# VisualEar-2_0.net
KiCad netlist of a schematic drawn in EAGLE
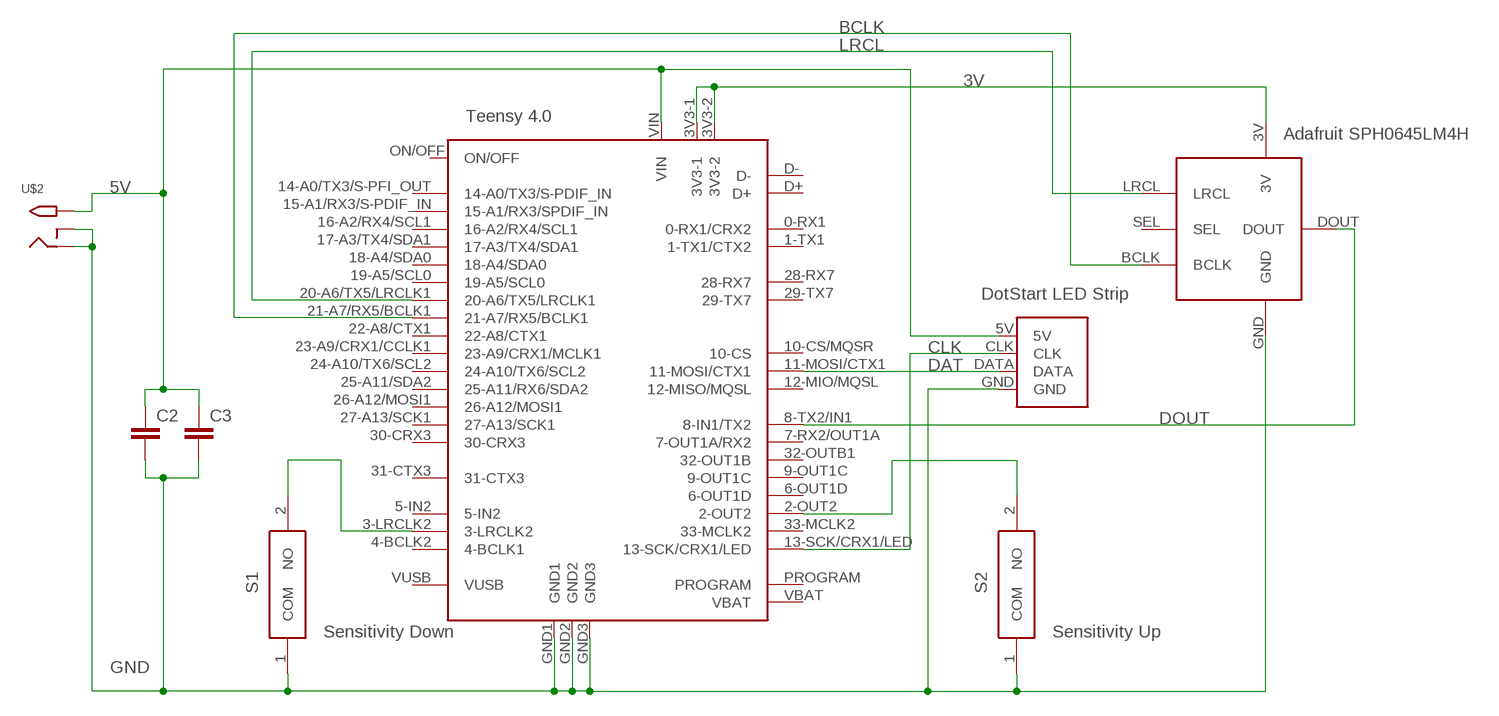
[diagram p0: schematic, sheet 1]

(export (version "E")
  (design (tool "Eeschema 10.0.6"))
  (components
    (comp (ref "C2")
      (value "CAPPTH")
      (footprint "eagle-import:CAP-PTH-SMALL")
      (libsource (lib "eagle-import") (part "CAPPTH"))
    )
    (comp (ref "C3")
      (value "CAPPTH")
      (footprint "eagle-import:CAP-PTH-SMALL")
      (libsource (lib "eagle-import") (part "CAPPTH"))
    )
    (comp (ref "S1")
      (value "TACTILE-SWITCHTHRU-HOLE")
      (footprint "eagle-import:CLICK-WEL")
      (libsource (lib "eagle-import") (part "TACTILE-SWITCHTHRU-HOLE"))
    )
    (comp (ref "S2")
      (value "TACTILE-SWITCHTHRU-HOLE")
      (footprint "eagle-import:CLICK-WEL")
      (libsource (lib "eagle-import") (part "TACTILE-SWITCHTHRU-HOLE"))
    )
    (comp (ref "U$1")
      (value "TEENSY40DIP")
      (footprint "eagle-import:TEENSY40-DIP")
      (libsource (lib "eagle-import") (part "TEENSY40DIP"))
    )
    (comp (ref "U$2")
      (value "2.1MMJACKTHM")
      (footprint "eagle-import:PJ-102A")
      (libsource (lib "eagle-import") (part "2.1MMJACKTHM"))
    )
    (comp (ref "U$3")
      (value "AF-I2S-MIC")
      (footprint "eagle-import:AF-I2S-MIC")
      (libsource (lib "eagle-import") (part "AF-I2S-MIC"))
    )
    (comp (ref "U$4")
      (value "LED-STRIP")
      (footprint "eagle-import:LED_STRIP")
      (libsource (lib "eagle-import") (part "LED-STRIP"))
    )
  )
  (nets
    (net (code "1") (name "/3V") (class "Default")
      (node (ref "U$1") (pin "3V3-1") (pinfunction "3V3-1_3V3-1") (pintype "bidirectional"))
      (node (ref "U$1") (pin "3V3-2") (pinfunction "3V3-2_3V3-2") (pintype "bidirectional"))
      (node (ref "U$3") (pin "3V") (pinfunction "3V_3V") (pintype "bidirectional"))
    )
    (net (code "2") (name "/5V") (class "Default")
      (node (ref "C2") (pin "1") (pinfunction "1_1") (pintype "passive"))
      (node (ref "C3") (pin "1") (pinfunction "1_1") (pintype "passive"))
      (node (ref "U$1") (pin "VIN") (pinfunction "VIN_VIN") (pintype "bidirectional"))
      (node (ref "U$2") (pin "TIP") (pinfunction "TIP_TIP") (pintype "bidirectional"))
      (node (ref "U$4") (pin "5V") (pinfunction "5V_5V") (pintype "bidirectional"))
    )
    (net (code "3") (name "/BCLK") (class "Default")
      (node (ref "U$1") (pin "21-A7/RX5/BCLK1") (pinfunction "21-A7/RX5/BCLK1_21-A7/RX5/BCLK1") (pintype "bidirectional"))
      (node (ref "U$3") (pin "BCLK") (pinfunction "BCLK_BCLK") (pintype "bidirectional"))
    )
    (net (code "4") (name "/CLK") (class "Default")
      (node (ref "U$1") (pin "13-SCK/CRX1/LED") (pinfunction "13-SCK/CRX1/LED_13-SCK/CRX1/LED") (pintype "bidirectional"))
      (node (ref "U$4") (pin "CLK") (pinfunction "CLK_CLK") (pintype "bidirectional"))
    )
    (net (code "5") (name "/DAT") (class "Default")
      (node (ref "U$1") (pin "11-MOSI/CTX1") (pinfunction "11-MOSI/CTX1_11-MOSI/CTX1") (pintype "bidirectional"))
      (node (ref "U$4") (pin "DATA") (pinfunction "DATA_DATA") (pintype "bidirectional"))
    )
    (net (code "6") (name "/DOUT") (class "Default")
      (node (ref "U$1") (pin "8-TX2/IN1") (pinfunction "8-IN1/TX2_8-TX2/IN1") (pintype "bidirectional"))
      (node (ref "U$3") (pin "DOUT") (pinfunction "DOUT_DOUT") (pintype "bidirectional"))
    )
    (net (code "7") (name "/GND") (class "Default")
      (node (ref "C2") (pin "2") (pinfunction "2_2") (pintype "passive"))
      (node (ref "C3") (pin "2") (pinfunction "2_2") (pintype "passive"))
      (node (ref "S1") (pin "1") (pinfunction "COM_1") (pintype "bidirectional"))
      (node (ref "S2") (pin "1") (pinfunction "COM_1") (pintype "bidirectional"))
      (node (ref "U$1") (pin "GND1") (pinfunction "GND1_GND1") (pintype "bidirectional"))
      (node (ref "U$1") (pin "GND2") (pinfunction "GND2_GND2") (pintype "bidirectional"))
      (node (ref "U$1") (pin "GND3") (pinfunction "GND3_GND3") (pintype "bidirectional"))
      (node (ref "U$2") (pin "RING") (pinfunction "RING_RING") (pintype "bidirectional"))
      (node (ref "U$2") (pin "RING_SW") (pinfunction "RING_SW_RING_SW") (pintype "bidirectional"))
      (node (ref "U$3") (pin "GND") (pinfunction "GND_GND") (pintype "bidirectional"))
      (node (ref "U$4") (pin "GND") (pinfunction "GND_GND") (pintype "bidirectional"))
    )
    (net (code "8") (name "/LRCL") (class "Default")
      (node (ref "U$1") (pin "20-A6/TX5/LRCLK1") (pinfunction "20-A6/TX5/LRCLK1_20-A6/TX5/LRCLK1") (pintype "bidirectional"))
      (node (ref "U$3") (pin "LRCL") (pinfunction "LRCL_LRCL") (pintype "bidirectional"))
    )
    (net (code "9") (name "Net-(S1-NO)") (class "Default")
      (node (ref "S1") (pin "2") (pinfunction "NO_2") (pintype "bidirectional"))
      (node (ref "U$1") (pin "3-LRCLK2") (pinfunction "3-LRCLK2_3-LRCLK2") (pintype "bidirectional"))
    )
    (net (code "10") (name "Net-(S2-NO)") (class "Default")
      (node (ref "S2") (pin "2") (pinfunction "NO_2") (pintype "bidirectional"))
      (node (ref "U$1") (pin "2-OUT2") (pinfunction "2-OUT2_2-OUT2") (pintype "bidirectional"))
    )
    (net (code "11") (name "unconnected-(U$1-0-RX1{slash}CRX2-Pad0-RX1)") (class "Default")
      (node (ref "U$1") (pin "0-RX1") (pinfunction "0-RX1/CRX2_0-RX1") (pintype "bidirectional"))
    )
    (net (code "12") (name "unconnected-(U$1-1-TX1{slash}CTX2-Pad1-TX1)") (class "Default")
      (node (ref "U$1") (pin "1-TX1") (pinfunction "1-TX1/CTX2_1-TX1") (pintype "bidirectional"))
    )
    (net (code "13") (name "unconnected-(U$1-4-BCLK1-Pad4-BCLK2)") (class "Default")
      (node (ref "U$1") (pin "4-BCLK2") (pinfunction "4-BCLK1_4-BCLK2") (pintype "bidirectional"))
    )
    (net (code "14") (name "unconnected-(U$1-7-OUT1A{slash}RX2-Pad7-RX2{slash}OUT1A)") (class "Default")
      (node (ref "U$1") (pin "7-RX2/OUT1A") (pinfunction "7-OUT1A/RX2_7-RX2/OUT1A") (pintype "bidirectional"))
    )
    (net (code "15") (name "unconnected-(U$1-10-CS-Pad10-CS{slash}MQSR)") (class "Default")
      (node (ref "U$1") (pin "10-CS/MQSR") (pinfunction "10-CS_10-CS/MQSR") (pintype "bidirectional"))
    )
    (net (code "16") (name "unconnected-(U$1-12-MISO{slash}MQSL-Pad12-MIO{slash}MQSL)") (class "Default")
      (node (ref "U$1") (pin "12-MIO/MQSL") (pinfunction "12-MISO/MQSL_12-MIO/MQSL") (pintype "bidirectional"))
    )
    (net (code "17") (name "unconnected-(U$1-14-A0{slash}TX3{slash}S-PDIF_IN-Pad14-A0{slash}TX3{slash}S-PFI_OUT)") (class "Default")
      (node (ref "U$1") (pin "14-A0/TX3/S-PFI_OUT") (pinfunction "14-A0/TX3/S-PDIF_IN_14-A0/TX3/S-PFI_OUT") (pintype "bidirectional"))
    )
    (net (code "18") (name "unconnected-(U$1-15-A1{slash}RX3{slash}SPDIF_IN-Pad15-A1{slash}RX3{slash}S-PDIF_IN)") (class "Default")
      (node (ref "U$1") (pin "15-A1/RX3/S-PDIF_IN") (pinfunction "15-A1/RX3/SPDIF_IN_15-A1/RX3/S-PDIF_IN") (pintype "bidirectional"))
    )
    (net (code "19") (name "unconnected-(U$1-23-A9{slash}CRX1{slash}MCLK1-Pad23-A9{slash}CRX1{slash}CCLK1)") (class "Default")
      (node (ref "U$1") (pin "23-A9/CRX1/CCLK1") (pinfunction "23-A9/CRX1/MCLK1_23-A9/CRX1/CCLK1") (pintype "bidirectional"))
    )
    (net (code "20") (name "unconnected-(U$1-25-A11{slash}RX6{slash}SDA2-Pad25-A11{slash}SDA2)") (class "Default")
      (node (ref "U$1") (pin "25-A11/SDA2") (pinfunction "25-A11/RX6/SDA2_25-A11/SDA2") (pintype "bidirectional"))
    )
    (net (code "21") (name "unconnected-(U$1-32-OUT1B-Pad32-OUTB1)") (class "Default")
      (node (ref "U$1") (pin "32-OUTB1") (pinfunction "32-OUT1B_32-OUTB1") (pintype "bidirectional"))
    )
    (net (code "22") (name "unconnected-(U$1-Pad5-IN2)") (class "Default")
      (node (ref "U$1") (pin "5-IN2") (pinfunction "5-IN2_5-IN2") (pintype "bidirectional"))
    )
    (net (code "23") (name "unconnected-(U$1-Pad6-OUT1D)") (class "Default")
      (node (ref "U$1") (pin "6-OUT1D") (pinfunction "6-OUT1D_6-OUT1D") (pintype "bidirectional"))
    )
    (net (code "24") (name "unconnected-(U$1-Pad9-OUT1C)") (class "Default")
      (node (ref "U$1") (pin "9-OUT1C") (pinfunction "9-OUT1C_9-OUT1C") (pintype "bidirectional"))
    )
    (net (code "25") (name "unconnected-(U$1-Pad16-A2{slash}RX4{slash}SCL1)") (class "Default")
      (node (ref "U$1") (pin "16-A2/RX4/SCL1") (pinfunction "16-A2/RX4/SCL1_16-A2/RX4/SCL1") (pintype "bidirectional"))
    )
    (net (code "26") (name "unconnected-(U$1-Pad17-A3{slash}TX4{slash}SDA1)") (class "Default")
      (node (ref "U$1") (pin "17-A3/TX4/SDA1") (pinfunction "17-A3/TX4/SDA1_17-A3/TX4/SDA1") (pintype "bidirectional"))
    )
    (net (code "27") (name "unconnected-(U$1-Pad18-A4{slash}SDA0)") (class "Default")
      (node (ref "U$1") (pin "18-A4/SDA0") (pinfunction "18-A4/SDA0_18-A4/SDA0") (pintype "bidirectional"))
    )
    (net (code "28") (name "unconnected-(U$1-Pad19-A5{slash}SCL0)") (class "Default")
      (node (ref "U$1") (pin "19-A5/SCL0") (pinfunction "19-A5/SCL0_19-A5/SCL0") (pintype "bidirectional"))
    )
    (net (code "29") (name "unconnected-(U$1-Pad22-A8{slash}CTX1)") (class "Default")
      (node (ref "U$1") (pin "22-A8/CTX1") (pinfunction "22-A8/CTX1_22-A8/CTX1") (pintype "bidirectional"))
    )
    (net (code "30") (name "unconnected-(U$1-Pad24-A10{slash}TX6{slash}SCL2)") (class "Default")
      (node (ref "U$1") (pin "24-A10/TX6/SCL2") (pinfunction "24-A10/TX6/SCL2_24-A10/TX6/SCL2") (pintype "bidirectional"))
    )
    (net (code "31") (name "unconnected-(U$1-Pad26-A12{slash}MOSI1)") (class "Default")
      (node (ref "U$1") (pin "26-A12/MOSI1") (pinfunction "26-A12/MOSI1_26-A12/MOSI1") (pintype "bidirectional"))
    )
    (net (code "32") (name "unconnected-(U$1-Pad27-A13{slash}SCK1)") (class "Default")
      (node (ref "U$1") (pin "27-A13/SCK1") (pinfunction "27-A13/SCK1_27-A13/SCK1") (pintype "bidirectional"))
    )
    (net (code "33") (name "unconnected-(U$1-Pad28-RX7)") (class "Default")
      (node (ref "U$1") (pin "28-RX7") (pinfunction "28-RX7_28-RX7") (pintype "bidirectional"))
    )
    (net (code "34") (name "unconnected-(U$1-Pad29-TX7)") (class "Default")
      (node (ref "U$1") (pin "29-TX7") (pinfunction "29-TX7_29-TX7") (pintype "bidirectional"))
    )
    (net (code "35") (name "unconnected-(U$1-Pad30-CRX3)") (class "Default")
      (node (ref "U$1") (pin "30-CRX3") (pinfunction "30-CRX3_30-CRX3") (pintype "bidirectional"))
    )
    (net (code "36") (name "unconnected-(U$1-Pad31-CTX3)") (class "Default")
      (node (ref "U$1") (pin "31-CTX3") (pinfunction "31-CTX3_31-CTX3") (pintype "bidirectional"))
    )
    (net (code "37") (name "unconnected-(U$1-Pad33-MCLK2)") (class "Default")
      (node (ref "U$1") (pin "33-MCLK2") (pinfunction "33-MCLK2_33-MCLK2") (pintype "bidirectional"))
    )
    (net (code "38") (name "unconnected-(U$1-PadD+)") (class "Default")
      (node (ref "U$1") (pin "D+") (pinfunction "D+_D+") (pintype "bidirectional"))
    )
    (net (code "39") (name "unconnected-(U$1-PadD-)") (class "Default")
      (node (ref "U$1") (pin "D-") (pinfunction "D-_D-") (pintype "bidirectional"))
    )
    (net (code "40") (name "unconnected-(U$1-PadON{slash}OFF)") (class "Default")
      (node (ref "U$1") (pin "ON/OFF") (pinfunction "ON/OFF_ON/OFF") (pintype "bidirectional"))
    )
    (net (code "41") (name "unconnected-(U$1-PadPROGRAM)") (class "Default")
      (node (ref "U$1") (pin "PROGRAM") (pinfunction "PROGRAM_PROGRAM") (pintype "bidirectional"))
    )
    (net (code "42") (name "unconnected-(U$1-PadVBAT)") (class "Default")
      (node (ref "U$1") (pin "VBAT") (pinfunction "VBAT_VBAT") (pintype "bidirectional"))
    )
    (net (code "43") (name "unconnected-(U$1-PadVUSB)") (class "Default")
      (node (ref "U$1") (pin "VUSB") (pinfunction "VUSB_VUSB") (pintype "bidirectional"))
    )
    (net (code "44") (name "unconnected-(U$3-PadSEL)") (class "Default")
      (node (ref "U$3") (pin "SEL") (pinfunction "SEL_SEL") (pintype "bidirectional"))
    )
  )
)
